# Hall_sensor.net
KiCad netlist of a schematic drawn in Altium Designer
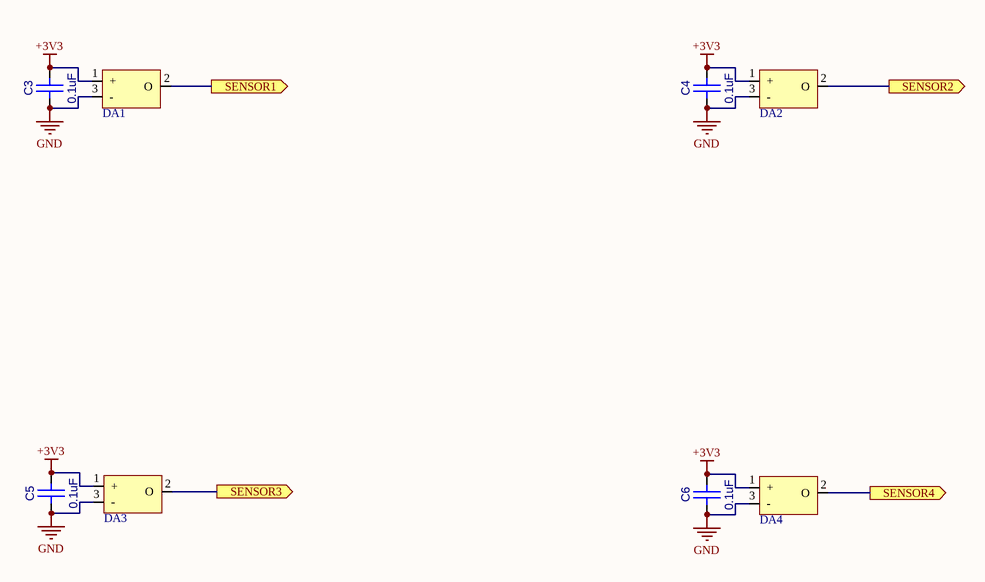
[diagram p0: Hall_sensor.SchDoc]

(export (version "E")
  (design (tool "Eeschema 10.0.6"))
  (components
    (comp (ref "C3")
      (value "0.1uF")
      (footprint "CC0603")
      (description "CC0603")
      (libsource (lib "gprs_modem_2") (part "CC0603"))
    )
    (comp (ref "C4")
      (value "0.1uF")
      (footprint "CC0603")
      (description "CC0603")
      (libsource (lib "gprs_modem_2") (part "CC0603"))
    )
    (comp (ref "C5")
      (value "0.1uF")
      (footprint "CC0603")
      (description "CC0603")
      (libsource (lib "gprs_modem_2") (part "CC0603"))
    )
    (comp (ref "C6")
      (value "0.1uF")
      (footprint "CC0603")
      (description "CC0603")
      (libsource (lib "gprs_modem_2") (part "CC0603"))
    )
    (comp (ref "DA1")
      (value "DRV5033AJQDBZR")
      (footprint "SOT-23(123)")
      (description "Hall sensor")
      (libsource (lib "gprs_modem_2") (part "DRV5033"))
    )
    (comp (ref "DA2")
      (value "DRV5033AJQDBZR")
      (footprint "SOT-23(123)")
      (description "Hall sensor")
      (libsource (lib "gprs_modem_2") (part "DRV5033"))
    )
    (comp (ref "DA3")
      (value "DRV5033AJQDBZR")
      (footprint "SOT-23(123)")
      (description "Hall sensor")
      (libsource (lib "gprs_modem_2") (part "DRV5033"))
    )
    (comp (ref "DA4")
      (value "DRV5033AJQDBZR")
      (footprint "SOT-23(123)")
      (description "Hall sensor")
      (libsource (lib "gprs_modem_2") (part "DRV5033"))
    )
  )
  (nets
    (net (code "1") (name "+3V3") (class "Default")
      (node (ref "C3") (pin "2") (pinfunction "B_2") (pintype "passive"))
      (node (ref "C4") (pin "2") (pinfunction "B_2") (pintype "passive"))
      (node (ref "C5") (pin "2") (pinfunction "B_2") (pintype "passive"))
      (node (ref "C6") (pin "2") (pinfunction "B_2") (pintype "passive"))
      (node (ref "DA1") (pin "1") (pinfunction "+_1") (pintype "passive"))
      (node (ref "DA2") (pin "1") (pinfunction "+_1") (pintype "passive"))
      (node (ref "DA3") (pin "1") (pinfunction "+_1") (pintype "passive"))
      (node (ref "DA4") (pin "1") (pinfunction "+_1") (pintype "passive"))
    )
    (net (code "2") (name "/SENSOR1") (class "Default")
      (node (ref "DA1") (pin "2") (pinfunction "O_2") (pintype "passive"))
    )
    (net (code "3") (name "/SENSOR2") (class "Default")
      (node (ref "DA2") (pin "2") (pinfunction "O_2") (pintype "passive"))
    )
    (net (code "4") (name "/SENSOR3") (class "Default")
      (node (ref "DA3") (pin "2") (pinfunction "O_2") (pintype "passive"))
    )
    (net (code "5") (name "/SENSOR4") (class "Default")
      (node (ref "DA4") (pin "2") (pinfunction "O_2") (pintype "passive"))
    )
    (net (code "6") (name "GND") (class "Default")
      (node (ref "C3") (pin "1") (pinfunction "A_1") (pintype "passive"))
      (node (ref "C4") (pin "1") (pinfunction "A_1") (pintype "passive"))
      (node (ref "C5") (pin "1") (pinfunction "A_1") (pintype "passive"))
      (node (ref "C6") (pin "1") (pinfunction "A_1") (pintype "passive"))
      (node (ref "DA1") (pin "3") (pinfunction "-_3") (pintype "passive"))
      (node (ref "DA2") (pin "3") (pinfunction "-_3") (pintype "passive"))
      (node (ref "DA3") (pin "3") (pinfunction "-_3") (pintype "passive"))
      (node (ref "DA4") (pin "3") (pinfunction "-_3") (pintype "passive"))
    )
  )
)
